# power.net
KiCad netlist of a schematic drawn in Altium Designer
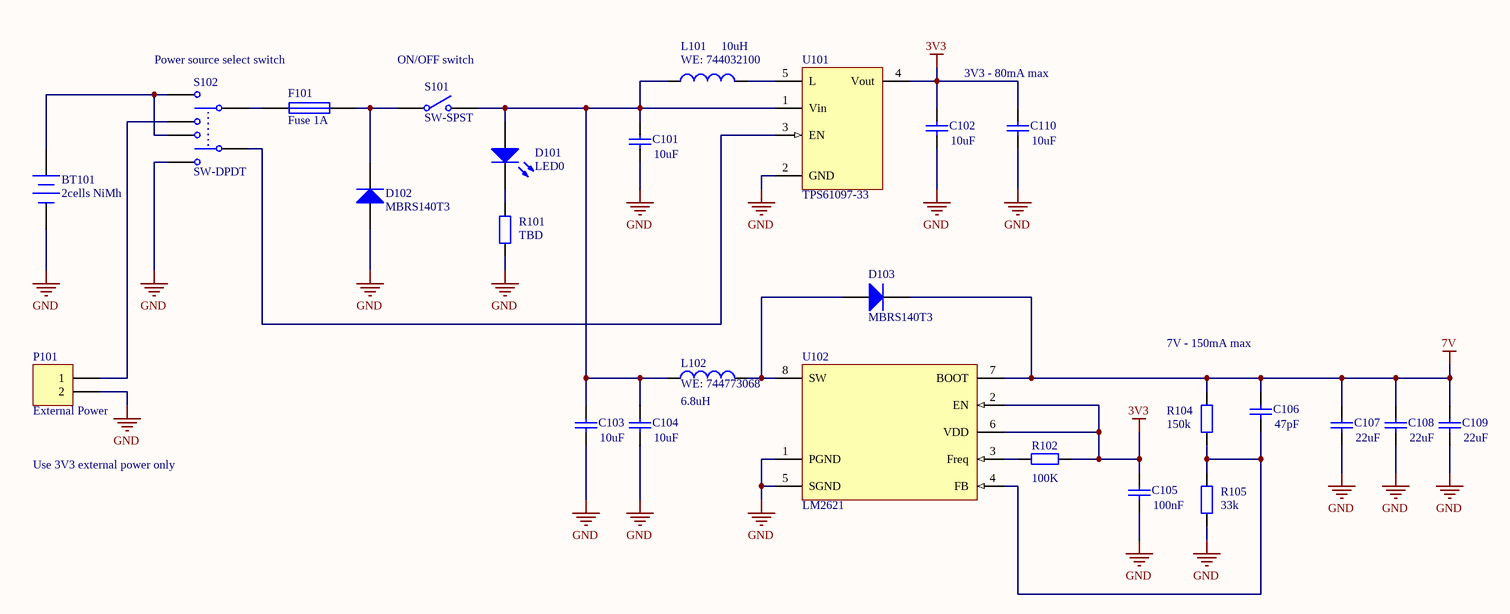
[diagram p0: power.SchDoc]

(export (version "E")
  (design (tool "Eeschema 10.0.6"))
  (components
    (comp (ref "BT101")
      (value "2cells NiMh")
      (footprint "BAT-2")
      (description "Multicell Battery")
      (fields (field (name "PUBLISHER") "Altium Limited"))
      (libsource (lib "Miscellaneous Devices") (part "Battery"))
    )
    (comp (ref "C101")
      (value "10uF")
      (footprint "2012[0805]")
      (description "Capacitor")
      (fields (field (name "Comment") "10uF 10V X5R 0805") (field (name "PUBLISHER") "Altium Limited"))
      (libsource (lib "Miscellaneous Devices") (part "Cap"))
    )
    (comp (ref "C102")
      (value "10uF")
      (footprint "2012[0805]")
      (description "Capacitor")
      (fields (field (name "Comment") "10uF 10V X5R 0805") (field (name "PUBLISHER") "Altium Limited"))
      (libsource (lib "Miscellaneous Devices") (part "Cap"))
    )
    (comp (ref "C103")
      (value "10uF")
      (footprint "2012[0805]")
      (description "Capacitor")
      (fields (field (name "Comment") "10uF 10V X5R 0805") (field (name "PUBLISHER") "Altium Limited"))
      (libsource (lib "Miscellaneous Devices") (part "Cap"))
    )
    (comp (ref "C104")
      (value "10uF")
      (footprint "2012[0805]")
      (description "Capacitor")
      (fields (field (name "Comment") "10uF 10V X5R 0805") (field (name "PUBLISHER") "Altium Limited"))
      (libsource (lib "Miscellaneous Devices") (part "Cap"))
    )
    (comp (ref "C105")
      (value "100nF")
      (footprint "1608[0603]")
      (description "Capacitor")
      (fields (field (name "Comment") "100nF 10V X7R 0603") (field (name "PUBLISHER") "Altium Limited"))
      (libsource (lib "Miscellaneous Devices") (part "Cap"))
    )
    (comp (ref "C106")
      (value "47pF")
      (footprint "1608[0603]")
      (description "Capacitor")
      (fields (field (name "Comment") "47pF 50V COG 0603") (field (name "PUBLISHER") "Altium Limited"))
      (libsource (lib "Miscellaneous Devices") (part "Cap"))
    )
    (comp (ref "C107")
      (value "22uF")
      (footprint "3225[1210]")
      (description "Capacitor")
      (fields (field (name "Comment") "22uF 16V X7R 1210") (field (name "PUBLISHER") "Altium Limited"))
      (libsource (lib "Miscellaneous Devices") (part "Cap"))
    )
    (comp (ref "C108")
      (value "22uF")
      (footprint "3225[1210]")
      (description "Capacitor")
      (fields (field (name "Comment") "22uF 16V X7R 1210") (field (name "PUBLISHER") "Altium Limited"))
      (libsource (lib "Miscellaneous Devices") (part "Cap"))
    )
    (comp (ref "C109")
      (value "22uF")
      (footprint "3225[1210]")
      (description "Capacitor")
      (fields (field (name "Comment") "22uF 16V X7R 1210") (field (name "PUBLISHER") "Altium Limited"))
      (libsource (lib "Miscellaneous Devices") (part "Cap"))
    )
    (comp (ref "C110")
      (value "10uF")
      (footprint "2012[0805]")
      (description "Capacitor")
      (fields (field (name "Comment") "10uF 10V X5R 0805") (field (name "PUBLISHER") "Altium Limited"))
      (libsource (lib "Miscellaneous Devices") (part "Cap"))
    )
    (comp (ref "D101")
      (value "LED0")
      (footprint "LED-0")
      (description "Typical INFRARED GaAs LED")
      (fields (field (name "PUBLISHER") "Altium Limited"))
      (libsource (lib "Miscellaneous Devices") (part "LED0"))
    )
    (comp (ref "D102")
      (value "MBRS140T3")
      (footprint "SMB")
      (description "Default Diode")
      (fields (field (name "PUBLISHER") "Altium Limited"))
      (libsource (lib "Miscellaneous Devices") (part "Diode"))
    )
    (comp (ref "D103")
      (value "MBRS140T3")
      (footprint "SMB")
      (description "Default Diode")
      (fields (field (name "PUBLISHER") "Altium Limited"))
      (libsource (lib "Miscellaneous Devices") (part "Diode"))
    )
    (comp (ref "F101")
      (value "Fuse 1A")
      (footprint "PIN-W2/E2.8")
      (description "Fuse")
      (fields (field (name "PUBLISHER") "Altium Limited"))
      (libsource (lib "Miscellaneous Devices") (part "Fuse 1"))
    )
    (comp (ref "L101")
      (value "WE: 744032100")
      (footprint "0402-A")
      (description "Inductor")
      (fields (field (name "ALTIUM_VALUE") "10uH") (field (name "PUBLISHER") "Altium Limited"))
      (libsource (lib "Miscellaneous Devices") (part "Inductor"))
    )
    (comp (ref "L102")
      (value "WE: 744773068")
      (footprint "0402-A")
      (description "Inductor")
      (fields (field (name "ALTIUM_VALUE") "6.8uH") (field (name "PUBLISHER") "Altium Limited"))
      (libsource (lib "Miscellaneous Devices") (part "Inductor"))
    )
    (comp (ref "P101")
      (value "External Power")
      (footprint "HDR1X2")
      (description "Header, 2-Pin")
      (fields (field (name "PUBLISHER") "Altium Limited"))
      (libsource (lib "Miscellaneous Connectors") (part "Header 2"))
    )
    (comp (ref "R101")
      (value "TBD")
      (footprint "1608[0603]")
      (description "Resistor")
      (fields (field (name "Comment") "Res 0603 TBD") (field (name "PUBLISHER") "Altium Limited"))
      (libsource (lib "Miscellaneous Devices") (part "Res2"))
    )
    (comp (ref "R102")
      (value "100K")
      (footprint "1608[0603]")
      (description "Resistor")
      (fields (field (name "Comment") "100k 0603") (field (name "PUBLISHER") "Altium Limited"))
      (libsource (lib "") (part "Res2_1"))
    )
    (comp (ref "R104")
      (value "150k")
      (footprint "1608[0603]")
      (description "Resistor")
      (fields (field (name "Comment") "150k 0603") (field (name "PUBLISHER") "Altium Limited"))
      (libsource (lib "Miscellaneous Devices") (part "Res2"))
    )
    (comp (ref "R105")
      (value "33k")
      (footprint "1608[0603]")
      (description "Resistor")
      (fields (field (name "Comment") "33k 0603") (field (name "PUBLISHER") "Altium Limited"))
      (libsource (lib "Miscellaneous Devices") (part "Res2"))
    )
    (comp (ref "S101")
      (value "SW-SPST")
      (footprint "SPST-2")
      (description "Single-Pole, Single-Throw Switch")
      (fields (field (name "PUBLISHER") "Altium Limited"))
      (libsource (lib "Miscellaneous Devices") (part "SW-SPST"))
    )
    (comp (ref "S102")
      (value "SW-DPDT")
      (footprint "DPDT-6")
      (description "Double-Pole, Double-Throw Switch")
      (fields (field (name "PUBLISHER") "Altium Limited"))
      (libsource (lib "Miscellaneous Devices") (part "SW-DPDT"))
    )
    (comp (ref "U101")
      (value "TPS61097-33")
      (footprint "DBV005")
      (description "LOW INPUT VOLTAGE SYNCHRONOUS BOOST CONVERTER  WITH LOW QUIESCENT CURRENT")
      (libsource (lib "Oufff_Lib2") (part "TPS61097"))
    )
    (comp (ref "U102")
      (value "LM2621")
      (footprint "MUA08A")
      (description "Low Input Voltage, Step-Up DC-DC Converter")
      (libsource (lib "Oufff_Lib2") (part "LM2621"))
    )
  )
  (nets
    (net (code "1") (name "3V3") (class "Default")
      (node (ref "C102") (pin "2") (pinfunction "2_2") (pintype "passive"))
      (node (ref "C105") (pin "2") (pinfunction "2_2") (pintype "passive"))
      (node (ref "C110") (pin "2") (pinfunction "2_2") (pintype "passive"))
      (node (ref "R102") (pin "2") (pinfunction "2_2") (pintype "passive"))
      (node (ref "U101") (pin "4") (pinfunction "Vout_4") (pintype "power_in"))
      (node (ref "U102") (pin "2") (pinfunction "EN_2") (pintype "input"))
      (node (ref "U102") (pin "6") (pinfunction "VDD_6") (pintype "power_in"))
    )
    (net (code "2") (name "7V") (class "Default")
      (node (ref "C106") (pin "2") (pinfunction "2_2") (pintype "passive"))
      (node (ref "C107") (pin "2") (pinfunction "2_2") (pintype "passive"))
      (node (ref "C108") (pin "2") (pinfunction "2_2") (pintype "passive"))
      (node (ref "C109") (pin "2") (pinfunction "2_2") (pintype "passive"))
      (node (ref "D103") (pin "2") (pinfunction "K_2") (pintype "passive"))
      (node (ref "R104") (pin "2") (pinfunction "2_2") (pintype "passive"))
      (node (ref "U102") (pin "7") (pinfunction "BOOT_7") (pintype "power_in"))
    )
    (net (code "3") (name "GND") (class "Default")
      (node (ref "BT101") (pin "2") (pinfunction "-_2") (pintype "passive"))
      (node (ref "C101") (pin "1") (pinfunction "1_1") (pintype "passive"))
      (node (ref "C102") (pin "1") (pinfunction "1_1") (pintype "passive"))
      (node (ref "C103") (pin "1") (pinfunction "1_1") (pintype "passive"))
      (node (ref "C104") (pin "1") (pinfunction "1_1") (pintype "passive"))
      (node (ref "C105") (pin "1") (pinfunction "1_1") (pintype "passive"))
      (node (ref "C107") (pin "1") (pinfunction "1_1") (pintype "passive"))
      (node (ref "C108") (pin "1") (pinfunction "1_1") (pintype "passive"))
      (node (ref "C109") (pin "1") (pinfunction "1_1") (pintype "passive"))
      (node (ref "C110") (pin "1") (pinfunction "1_1") (pintype "passive"))
      (node (ref "D102") (pin "1") (pinfunction "A_1") (pintype "passive"))
      (node (ref "P101") (pin "2") (pinfunction "2_2") (pintype "passive"))
      (node (ref "R101") (pin "1") (pinfunction "1_1") (pintype "passive"))
      (node (ref "R105") (pin "1") (pinfunction "1_1") (pintype "passive"))
      (node (ref "S102") (pin "6") (pinfunction "6_6") (pintype "passive"))
      (node (ref "U101") (pin "2") (pinfunction "GND_2") (pintype "power_in"))
      (node (ref "U102") (pin "1") (pinfunction "PGND_1") (pintype "power_in"))
      (node (ref "U102") (pin "5") (pinfunction "SGND_5") (pintype "power_in"))
    )
    (net (code "4") (name "Net-(BT101-+)") (class "Default")
      (node (ref "BT101") (pin "1") (pinfunction "+_1") (pintype "passive"))
      (node (ref "S102") (pin "2") (pinfunction "2_2") (pintype "passive"))
      (node (ref "S102") (pin "5") (pinfunction "5_5") (pintype "passive"))
    )
    (net (code "5") (name "Net-(D101-A)") (class "Default")
      (node (ref "C101") (pin "2") (pinfunction "2_2") (pintype "passive"))
      (node (ref "C103") (pin "2") (pinfunction "2_2") (pintype "passive"))
      (node (ref "C104") (pin "2") (pinfunction "2_2") (pintype "passive"))
      (node (ref "D101") (pin "1") (pinfunction "A_1") (pintype "passive"))
      (node (ref "L101") (pin "1") (pinfunction "1_1") (pintype "passive"))
      (node (ref "L102") (pin "1") (pinfunction "1_1") (pintype "passive"))
      (node (ref "S101") (pin "2") (pinfunction "NO_2") (pintype "passive"))
      (node (ref "U101") (pin "1") (pinfunction "Vin_1") (pintype "power_in"))
    )
    (net (code "6") (name "Net-(D101-K)") (class "Default")
      (node (ref "D101") (pin "2") (pinfunction "K_2") (pintype "passive"))
      (node (ref "R101") (pin "2") (pinfunction "2_2") (pintype "passive"))
    )
    (net (code "7") (name "Net-(D102-K)") (class "Default")
      (node (ref "D102") (pin "2") (pinfunction "K_2") (pintype "passive"))
      (node (ref "F101") (pin "2") (pinfunction "2_2") (pintype "passive"))
      (node (ref "S101") (pin "1") (pinfunction "COMMON_1") (pintype "passive"))
    )
    (net (code "8") (name "Net-(D103-A)") (class "Default")
      (node (ref "D103") (pin "1") (pinfunction "A_1") (pintype "passive"))
      (node (ref "L102") (pin "2") (pinfunction "2_2") (pintype "passive"))
      (node (ref "U102") (pin "8") (pinfunction "SW_8") (pintype "power_in"))
    )
    (net (code "9") (name "Net-(F101-Pad1)") (class "Default")
      (node (ref "F101") (pin "1") (pinfunction "1_1") (pintype "passive"))
      (node (ref "S102") (pin "1") (pinfunction "1_1") (pintype "passive"))
    )
    (net (code "10") (name "Net-(P101-Pad1)") (class "Default")
      (node (ref "P101") (pin "1") (pinfunction "1_1") (pintype "passive"))
      (node (ref "S102") (pin "3") (pinfunction "3_3") (pintype "passive"))
    )
    (net (code "11") (name "Net-(U101-EN)") (class "Default")
      (node (ref "S102") (pin "4") (pinfunction "4_4") (pintype "passive"))
      (node (ref "U101") (pin "3") (pinfunction "EN_3") (pintype "input"))
    )
    (net (code "12") (name "Net-(U101-L)") (class "Default")
      (node (ref "L101") (pin "2") (pinfunction "2_2") (pintype "passive"))
      (node (ref "U101") (pin "5") (pinfunction "L_5") (pintype "power_in"))
    )
    (net (code "13") (name "Net-(U102-FB)") (class "Default")
      (node (ref "C106") (pin "1") (pinfunction "1_1") (pintype "passive"))
      (node (ref "R104") (pin "1") (pinfunction "1_1") (pintype "passive"))
      (node (ref "R105") (pin "2") (pinfunction "2_2") (pintype "passive"))
      (node (ref "U102") (pin "4") (pinfunction "FB_4") (pintype "input"))
    )
    (net (code "14") (name "Net-(U102-Freq)") (class "Default")
      (node (ref "R102") (pin "1") (pinfunction "1_1") (pintype "passive"))
      (node (ref "U102") (pin "3") (pinfunction "Freq_3") (pintype "input"))
    )
  )
)
